# template_attiny_44_soic-14.net
KiCad netlist of a schematic drawn in EAGLE
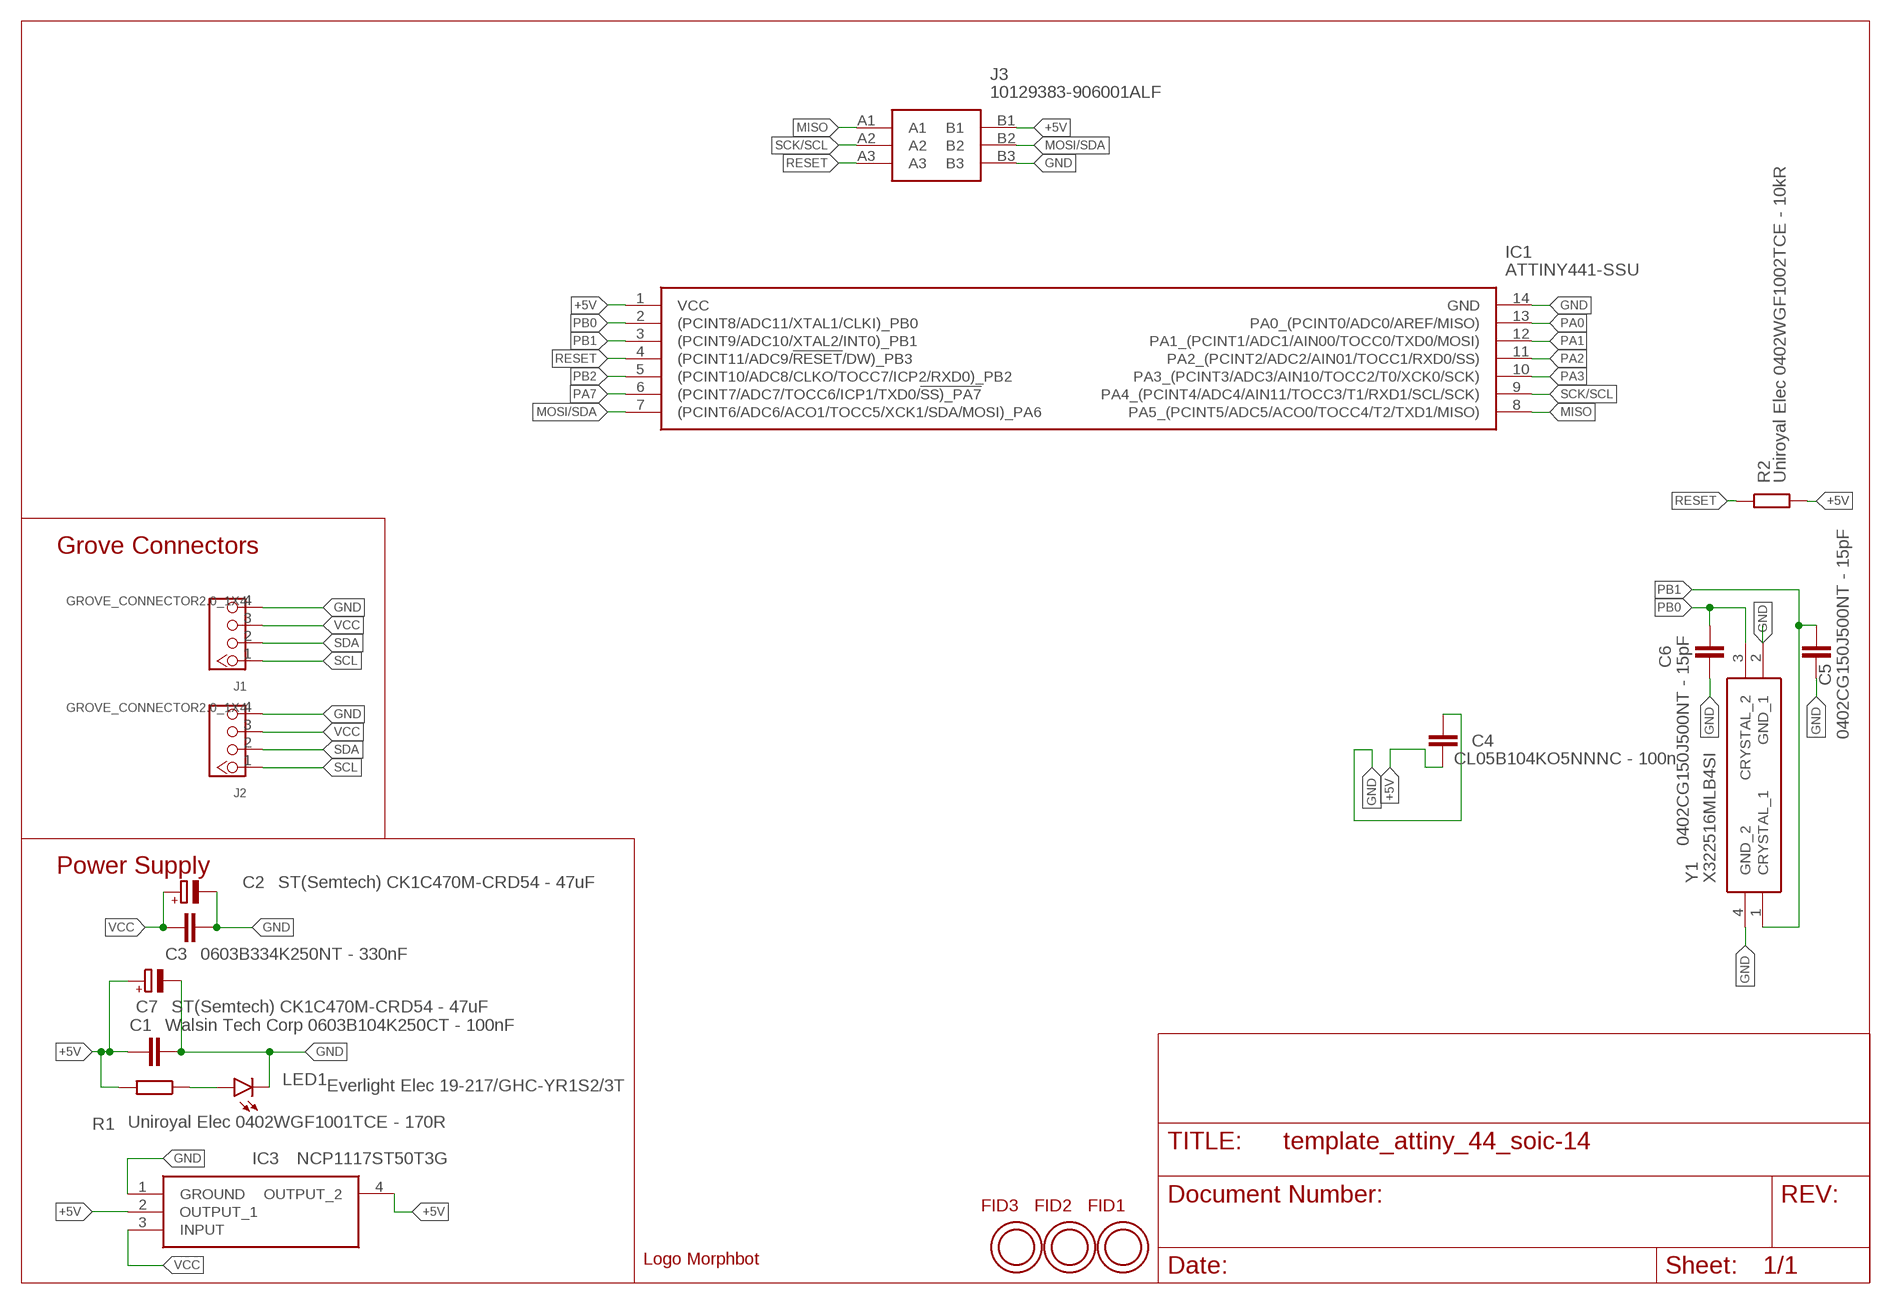
[diagram p0: schematic, sheet 1]

(export (version "E")
  (design (tool "Eeschema 10.0.6"))
  (components
    (comp (ref "C1")
      (value "Walsin Tech Corp 0603B104K250CT - 100nF")
      (footprint "eagle-import:C0603")
      (libsource (lib "eagle-import") (part "C-EUC0603"))
    )
    (comp (ref "C2")
      (value "ST(Semtech) CK1C470M-CRD54 - 47uF")
      (footprint "eagle-import:PANASONIC_C")
      (libsource (lib "eagle-import") (part "CPOL-EUC"))
    )
    (comp (ref "C3")
      (value "0603B334K250NT - 330nF")
      (footprint "eagle-import:C0603")
      (libsource (lib "eagle-import") (part "C-EUC0603"))
    )
    (comp (ref "C4")
      (value "CL05B104KO5NNNC - 100n")
      (footprint "eagle-import:C0402")
      (libsource (lib "eagle-import") (part "C-EUC0402"))
    )
    (comp (ref "C5")
      (value "0402CG150J500NT - 15pF")
      (footprint "eagle-import:C0402")
      (libsource (lib "eagle-import") (part "C-EUC0402"))
    )
    (comp (ref "C6")
      (value "0402CG150J500NT - 15pF")
      (footprint "eagle-import:C0402")
      (libsource (lib "eagle-import") (part "C-EUC0402"))
    )
    (comp (ref "C7")
      (value "ST(Semtech) CK1C470M-CRD54 - 47uF")
      (footprint "eagle-import:PANASONIC_C")
      (libsource (lib "eagle-import") (part "CPOL-EUC"))
    )
    (comp (ref "FID1")
      (value "OPEN-PNP-FIDUCIAL")
      (footprint "eagle-import:OPEN-PNP-FIDUCIAL")
      (libsource (lib "eagle-import") (part "OPEN-PNP-FIDUCIAL"))
    )
    (comp (ref "FID2")
      (value "OPEN-PNP-FIDUCIAL")
      (footprint "eagle-import:OPEN-PNP-FIDUCIAL")
      (libsource (lib "eagle-import") (part "OPEN-PNP-FIDUCIAL"))
    )
    (comp (ref "FID3")
      (value "OPEN-PNP-FIDUCIAL")
      (footprint "eagle-import:OPEN-PNP-FIDUCIAL")
      (libsource (lib "eagle-import") (part "OPEN-PNP-FIDUCIAL"))
    )
    (comp (ref "IC1")
      (value "ATTINY441-SSU")
      (footprint "eagle-import:SOIC127P600X175-14N")
      (fields (field (name "MOUSER_PART_NUMBER") "556-ATTINY441-SSU"))
      (libsource (lib "eagle-import") (part "ATTINY441-SSU"))
    )
    (comp (ref "IC3")
      (value "NCP1117ST50T3G")
      (footprint "eagle-import:SOT230P700X180-4N")
      (fields (field (name "MOUSER_PART_NUMBER") "863-NCP1117ST50T3G"))
      (libsource (lib "eagle-import") (part "NCP1117ST50T3G"))
    )
    (comp (ref "J1")
      (value "GROVE_CONNECTOR2.0_1X4")
      (footprint "eagle-import:2.0_1X4_STRAIGHT")
      (libsource (lib "eagle-import") (part "GROVE_CONNECTOR2.0_1X4"))
    )
    (comp (ref "J2")
      (value "GROVE_CONNECTOR2.0_1X4")
      (footprint "eagle-import:2.0_1X4_STRAIGHT")
      (libsource (lib "eagle-import") (part "GROVE_CONNECTOR2.0_1X4"))
    )
    (comp (ref "J3")
      (value "10129383-906001ALF")
      (footprint "eagle-import:10129383906001ALF")
      (fields (field (name "MOUSER_PART_NUMBER") "649-1012938390601ALF"))
      (libsource (lib "eagle-import") (part "10129383-906001ALF"))
    )
    (comp (ref "LED1")
      (value "Everlight Elec 19-217/GHC-YR1S2/3T")
      (footprint "eagle-import:CHIPLED_0603")
      (libsource (lib "eagle-import") (part "LEDCHIPLED_0603"))
    )
    (comp (ref "R1")
      (value "Uniroyal Elec 0402WGF1001TCE - 170R")
      (footprint "eagle-import:R0402")
      (libsource (lib "eagle-import") (part "R-EU_R0402"))
    )
    (comp (ref "R2")
      (value "Uniroyal Elec 0402WGF1002TCE - 10kR")
      (footprint "eagle-import:R0402")
      (libsource (lib "eagle-import") (part "R-EU_R0402"))
    )
    (comp (ref "U$1")
      (value "LOGO_MORPHBOT5MM")
      (footprint "eagle-import:LOGO_MORPHBOT")
      (libsource (lib "eagle-import") (part "LOGO_MORPHBOT5MM"))
    )
    (comp (ref "Y1")
      (value "X322516MLB4SI")
      (footprint "eagle-import:X322516MLB4SI")
      (libsource (lib "eagle-import") (part "X322516MLB4SI"))
    )
  )
  (nets
    (net (code "1") (name "+5V") (class "Default")
      (node (ref "C1") (pin "1") (pinfunction "1_1") (pintype "passive"))
      (node (ref "C4") (pin "1") (pinfunction "1_1") (pintype "passive"))
      (node (ref "C7") (pin "+") (pinfunction "+_+") (pintype "passive"))
      (node (ref "IC1") (pin "1") (pinfunction "VCC_1") (pintype "bidirectional"))
      (node (ref "IC3") (pin "2") (pinfunction "OUTPUT_1_2") (pintype "bidirectional"))
      (node (ref "IC3") (pin "4") (pinfunction "OUTPUT_2_4") (pintype "bidirectional"))
      (node (ref "J3") (pin "B1") (pinfunction "B1_B1") (pintype "bidirectional"))
      (node (ref "R1") (pin "2") (pinfunction "2_2") (pintype "passive"))
      (node (ref "R2") (pin "2") (pinfunction "2_2") (pintype "passive"))
    )
    (net (code "2") (name "GND") (class "Default")
      (node (ref "C1") (pin "2") (pinfunction "2_2") (pintype "passive"))
      (node (ref "C2") (pin "-") (pinfunction "-_-") (pintype "passive"))
      (node (ref "C3") (pin "1") (pinfunction "1_1") (pintype "passive"))
      (node (ref "C4") (pin "2") (pinfunction "2_2") (pintype "passive"))
      (node (ref "C5") (pin "1") (pinfunction "1_1") (pintype "passive"))
      (node (ref "C6") (pin "1") (pinfunction "1_1") (pintype "passive"))
      (node (ref "C7") (pin "-") (pinfunction "-_-") (pintype "passive"))
      (node (ref "IC1") (pin "14") (pinfunction "GND_14") (pintype "bidirectional"))
      (node (ref "IC3") (pin "1") (pinfunction "GROUND_1") (pintype "bidirectional"))
      (node (ref "J1") (pin "4") (pinfunction "4_4") (pintype "bidirectional"))
      (node (ref "J2") (pin "4") (pinfunction "4_4") (pintype "bidirectional"))
      (node (ref "J3") (pin "B3") (pinfunction "B3_B3") (pintype "bidirectional"))
      (node (ref "LED1") (pin "C") (pinfunction "C_C") (pintype "passive"))
      (node (ref "Y1") (pin "2") (pinfunction "GND_1_2") (pintype "bidirectional"))
      (node (ref "Y1") (pin "4") (pinfunction "GND_2_4") (pintype "bidirectional"))
    )
    (net (code "3") (name "MISO") (class "Default")
      (node (ref "IC1") (pin "8") (pinfunction "PA5_(PCINT5/ADC5/ACO0/TOCC4/T2/TXD1/MISO)_8") (pintype "bidirectional"))
      (node (ref "J3") (pin "A1") (pinfunction "A1_A1") (pintype "bidirectional"))
    )
    (net (code "4") (name "MOSI{slash}SDA") (class "Default")
      (node (ref "IC1") (pin "7") (pinfunction "(PCINT6/ADC6/ACO1/TOCC5/XCK1/SDA/MOSI)_PA6_7") (pintype "bidirectional"))
      (node (ref "J3") (pin "B2") (pinfunction "B2_B2") (pintype "bidirectional"))
    )
    (net (code "5") (name "Net-(LED1-PadA)") (class "Default")
      (node (ref "LED1") (pin "A") (pinfunction "A_A") (pintype "passive"))
      (node (ref "R1") (pin "1") (pinfunction "1_1") (pintype "passive"))
    )
    (net (code "6") (name "PA0") (class "Default")
      (node (ref "IC1") (pin "13") (pinfunction "PA0_(PCINT0/ADC0/AREF/MISO)_13") (pintype "bidirectional"))
    )
    (net (code "7") (name "PA1") (class "Default")
      (node (ref "IC1") (pin "12") (pinfunction "PA1_(PCINT1/ADC1/AIN00/TOCC0/TXD0/MOSI)_12") (pintype "bidirectional"))
    )
    (net (code "8") (name "PA2") (class "Default")
      (node (ref "IC1") (pin "11") (pinfunction "PA2_(PCINT2/ADC2/AIN01/TOCC1/RXD0/SS)_11") (pintype "bidirectional"))
    )
    (net (code "9") (name "PA3") (class "Default")
      (node (ref "IC1") (pin "10") (pinfunction "PA3_(PCINT3/ADC3/AIN10/TOCC2/T0/XCK0/SCK)_10") (pintype "bidirectional"))
    )
    (net (code "10") (name "PA7") (class "Default")
      (node (ref "IC1") (pin "6") (pinfunction "(PCINT7/ADC7/TOCC6/ICP1/TXD0/~{SS})_PA7_6") (pintype "bidirectional"))
    )
    (net (code "11") (name "PB0") (class "Default")
      (node (ref "C6") (pin "2") (pinfunction "2_2") (pintype "passive"))
      (node (ref "IC1") (pin "2") (pinfunction "(PCINT8/ADC11/XTAL1/CLKI)_PB0_2") (pintype "bidirectional"))
      (node (ref "Y1") (pin "3") (pinfunction "CRYSTAL_2_3") (pintype "bidirectional"))
    )
    (net (code "12") (name "PB1") (class "Default")
      (node (ref "C5") (pin "2") (pinfunction "2_2") (pintype "passive"))
      (node (ref "IC1") (pin "3") (pinfunction "(PCINT9/ADC10/XTAL2/INT0)_PB1_3") (pintype "bidirectional"))
      (node (ref "Y1") (pin "1") (pinfunction "CRYSTAL_1_1") (pintype "bidirectional"))
    )
    (net (code "13") (name "PB2") (class "Default")
      (node (ref "IC1") (pin "5") (pinfunction "(PCINT10/ADC8/CLKO/TOCC7/ICP2/RXD0)_PB2_5") (pintype "bidirectional"))
    )
    (net (code "14") (name "RESET") (class "Default")
      (node (ref "IC1") (pin "4") (pinfunction "(PCINT11/ADC9/~{RESET}/DW)_PB3_4") (pintype "bidirectional"))
      (node (ref "J3") (pin "A3") (pinfunction "A3_A3") (pintype "bidirectional"))
      (node (ref "R2") (pin "1") (pinfunction "1_1") (pintype "passive"))
    )
    (net (code "15") (name "SCK{slash}SCL") (class "Default")
      (node (ref "IC1") (pin "9") (pinfunction "PA4_(PCINT4/ADC4/AIN11/TOCC3/T1/RXD1/SCL/SCK)_9") (pintype "bidirectional"))
      (node (ref "J3") (pin "A2") (pinfunction "A2_A2") (pintype "bidirectional"))
    )
    (net (code "16") (name "SCL") (class "Default")
      (node (ref "J1") (pin "1") (pinfunction "1_1") (pintype "bidirectional"))
      (node (ref "J2") (pin "1") (pinfunction "1_1") (pintype "bidirectional"))
    )
    (net (code "17") (name "SDA") (class "Default")
      (node (ref "J1") (pin "2") (pinfunction "2_2") (pintype "bidirectional"))
      (node (ref "J2") (pin "2") (pinfunction "2_2") (pintype "bidirectional"))
    )
    (net (code "18") (name "VCC") (class "Default")
      (node (ref "C2") (pin "+") (pinfunction "+_+") (pintype "passive"))
      (node (ref "C3") (pin "2") (pinfunction "2_2") (pintype "passive"))
      (node (ref "IC3") (pin "3") (pinfunction "INPUT_3") (pintype "bidirectional"))
      (node (ref "J1") (pin "3") (pinfunction "3_3") (pintype "bidirectional"))
      (node (ref "J2") (pin "3") (pinfunction "3_3") (pintype "bidirectional"))
    )
  )
)
